# Final_out_1.net
KiCad netlist of a schematic drawn in Altium Designer
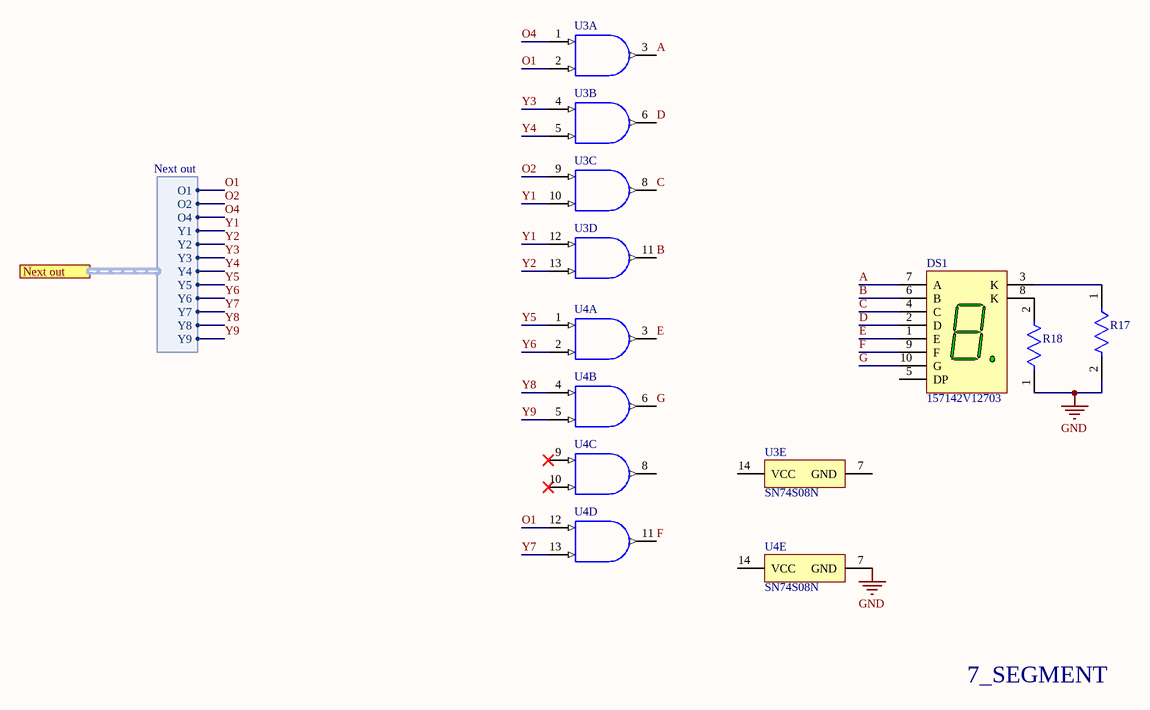
[diagram p0: Final out 1.SchDoc]

(export (version "E")
  (design (tool "Eeschema 10.0.6"))
  (components
    (comp (ref "DS1")
      (value "157142V12703")
      (footprint "WL-T7DS_L19W12.6H7.9")
      (description "157142V12703 7-Seg Display, Comm Cathode, Grn, 46Mcd Rohs Compliant: Yes")
      (libsource (lib "Altium Content Vault") (part "7 Segments_Green_CC_type 1"))
    )
    (comp (ref "R17")
      (value "MRS25000C1001FCT00")
      (footprint "FP-MRS25-MFG")
      (description "RES 1K OHM 0.6W 1% AXIAL")
      (fields (field (name "TOLERANCE") "1%"))
      (libsource (lib "Altium Content Vault") (part "1029c3af85768c4190bb7ad29bc67b5"))
    )
    (comp (ref "R18")
      (value "MRS25000C1001FCT00")
      (footprint "FP-MRS25-MFG")
      (description "RES 1K OHM 0.6W 1% AXIAL")
      (fields (field (name "TOLERANCE") "1%"))
      (libsource (lib "Altium Content Vault") (part "1029c3af85768c4190bb7ad29bc67b5"))
    )
    (comp (ref "U3")
      (value "SN74S08N")
      (footprint "N0014A")
      (description "Quad 2-input positive-AND gates, N0014A, TUBE")
      (fields
        (field (name "MANUFACTURER") "Texas Instruments")
        (field (name "GENERIC PART NUMBER") "SN74S08")
      )
      (libsource (lib "Altium Content Vault") (part "TI-AND-4-2IN-14"))
    )
    (comp (ref "U4")
      (value "SN74S08N")
      (footprint "N0014A")
      (description "Quad 2-input positive-AND gates, N0014A, TUBE")
      (fields
        (field (name "MANUFACTURER") "Texas Instruments")
        (field (name "GENERIC PART NUMBER") "SN74S08")
      )
      (libsource (lib "Altium Content Vault") (part "TI-AND-4-2IN-14"))
    )
  )
  (nets
    (net (code "3") (name "/A") (class "Default")
      (node (ref "DS1") (pin "7") (pinfunction "A_7") (pintype "passive"))
      (node (ref "U3") (pin "3") (pinfunction "1Y_3") (pintype "output"))
    )
    (net (code "4") (name "/B") (class "Default")
      (node (ref "DS1") (pin "6") (pinfunction "B_6") (pintype "passive"))
      (node (ref "U3") (pin "11") (pinfunction "4Y_11") (pintype "output"))
    )
    (net (code "5") (name "/C") (class "Default")
      (node (ref "DS1") (pin "4") (pinfunction "C_4") (pintype "passive"))
      (node (ref "U3") (pin "8") (pinfunction "3Y_8") (pintype "output"))
    )
    (net (code "6") (name "/D") (class "Default")
      (node (ref "DS1") (pin "2") (pinfunction "D_2") (pintype "passive"))
      (node (ref "U3") (pin "6") (pinfunction "2Y_6") (pintype "output"))
    )
    (net (code "7") (name "/E") (class "Default")
      (node (ref "DS1") (pin "1") (pinfunction "E_1") (pintype "passive"))
      (node (ref "U4") (pin "3") (pinfunction "1Y_3") (pintype "output"))
    )
    (net (code "8") (name "/F") (class "Default")
      (node (ref "DS1") (pin "9") (pinfunction "F_9") (pintype "passive"))
      (node (ref "U4") (pin "11") (pinfunction "4Y_11") (pintype "output"))
    )
    (net (code "9") (name "/G") (class "Default")
      (node (ref "DS1") (pin "10") (pinfunction "G_10") (pintype "passive"))
      (node (ref "U4") (pin "6") (pinfunction "2Y_6") (pintype "output"))
    )
    (net (code "10") (name "/O1") (class "Default")
      (node (ref "U3") (pin "2") (pinfunction "1B_2") (pintype "input"))
      (node (ref "U4") (pin "12") (pinfunction "4A_12") (pintype "input"))
    )
    (net (code "11") (name "/O2") (class "Default")
      (node (ref "U3") (pin "9") (pinfunction "3A_9") (pintype "input"))
    )
    (net (code "12") (name "/O4") (class "Default")
      (node (ref "U3") (pin "1") (pinfunction "1A_1") (pintype "input"))
    )
    (net (code "13") (name "/Y1") (class "Default")
      (node (ref "U3") (pin "10") (pinfunction "3B_10") (pintype "input"))
      (node (ref "U3") (pin "12") (pinfunction "4A_12") (pintype "input"))
    )
    (net (code "14") (name "/Y2") (class "Default")
      (node (ref "U3") (pin "13") (pinfunction "4B_13") (pintype "input"))
    )
    (net (code "15") (name "/Y3") (class "Default")
      (node (ref "U3") (pin "4") (pinfunction "2A_4") (pintype "input"))
    )
    (net (code "16") (name "/Y4") (class "Default")
      (node (ref "U3") (pin "5") (pinfunction "2B_5") (pintype "input"))
    )
    (net (code "17") (name "/Y5") (class "Default")
      (node (ref "U4") (pin "1") (pinfunction "1A_1") (pintype "input"))
    )
    (net (code "18") (name "/Y6") (class "Default")
      (node (ref "U4") (pin "2") (pinfunction "1B_2") (pintype "input"))
    )
    (net (code "19") (name "/Y7") (class "Default")
      (node (ref "U4") (pin "13") (pinfunction "4B_13") (pintype "input"))
    )
    (net (code "20") (name "/Y8") (class "Default")
      (node (ref "U4") (pin "4") (pinfunction "2A_4") (pintype "input"))
    )
    (net (code "21") (name "/Y9") (class "Default")
      (node (ref "U4") (pin "5") (pinfunction "2B_5") (pintype "input"))
    )
    (net (code "23") (name "GND") (class "Default")
      (node (ref "R17") (pin "2") (pinfunction "2_2") (pintype "passive"))
      (node (ref "R18") (pin "1") (pinfunction "1_1") (pintype "passive"))
      (node (ref "U4") (pin "7") (pinfunction "GND_7") (pintype "power_in"))
    )
    (net (code "24") (name "Net-(DS1-K-Pad3)") (class "Default")
      (node (ref "DS1") (pin "3") (pinfunction "K_3") (pintype "passive"))
      (node (ref "R17") (pin "1") (pinfunction "1_1") (pintype "passive"))
    )
    (net (code "25") (name "Net-(DS1-K-Pad8)") (class "Default")
      (node (ref "DS1") (pin "8") (pinfunction "K_8") (pintype "passive"))
      (node (ref "R18") (pin "2") (pinfunction "2_2") (pintype "passive"))
    )
    (net (code "26") (name "unconnected-(DS1-DP-Pad5)") (class "Default")
      (node (ref "DS1") (pin "5") (pinfunction "DP_5") (pintype "passive"))
    )
    (net (code "27") (name "unconnected-(U3E-GND-Pad7)") (class "Default")
      (node (ref "U3") (pin "7") (pinfunction "GND_7") (pintype "power_in"))
    )
    (net (code "28") (name "unconnected-(U3E-VCC-Pad14)") (class "Default")
      (node (ref "U3") (pin "14") (pinfunction "VCC_14") (pintype "power_in"))
    )
    (net (code "29") (name "unconnected-(U4C-3A-Pad9)") (class "Default")
      (node (ref "U4") (pin "9") (pinfunction "3A_9") (pintype "input+no_connect"))
    )
    (net (code "30") (name "unconnected-(U4C-3B-Pad10)") (class "Default")
      (node (ref "U4") (pin "10") (pinfunction "3B_10") (pintype "input+no_connect"))
    )
    (net (code "31") (name "unconnected-(U4C-3Y-Pad8)") (class "Default")
      (node (ref "U4") (pin "8") (pinfunction "3Y_8") (pintype "output"))
    )
    (net (code "32") (name "unconnected-(U4E-VCC-Pad14)") (class "Default")
      (node (ref "U4") (pin "14") (pinfunction "VCC_14") (pintype "power_in"))
    )
  )
)
